# INIR2-ME5Mount.net
KiCad netlist of a schematic drawn in EAGLE
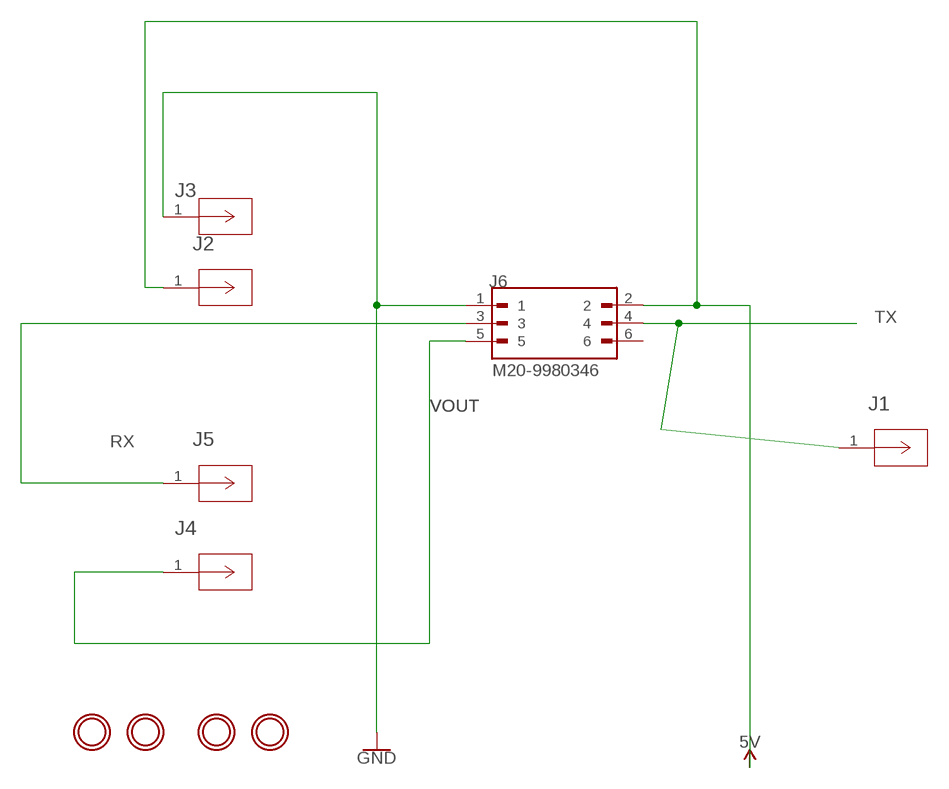
[diagram p0: schematic, sheet 1]

(export (version "E")
  (design (tool "Eeschema 10.0.6"))
  (components
    (comp (ref "J1")
      (value "450-3326-01-03-00")
      (footprint "eagle-import:CONN_450-3326-01-XX-00_CBN")
      (fields (field (name "COPYRIGHT") "Copyright (C) 2024 Ultra Librarian. All rights reserved."))
      (libsource (lib "eagle-import") (part "450-3326-01-03-00"))
    )
    (comp (ref "J2")
      (value "450-3326-01-03-00")
      (footprint "eagle-import:CONN_450-3326-01-XX-00_CBN")
      (fields (field (name "COPYRIGHT") "Copyright (C) 2024 Ultra Librarian. All rights reserved."))
      (libsource (lib "eagle-import") (part "450-3326-01-03-00"))
    )
    (comp (ref "J3")
      (value "450-3326-01-03-00")
      (footprint "eagle-import:CONN_450-3326-01-XX-00_CBN")
      (fields (field (name "COPYRIGHT") "Copyright (C) 2024 Ultra Librarian. All rights reserved."))
      (libsource (lib "eagle-import") (part "450-3326-01-03-00"))
    )
    (comp (ref "J4")
      (value "450-3326-01-03-00")
      (footprint "eagle-import:CONN_450-3326-01-XX-00_CBN")
      (fields (field (name "COPYRIGHT") "Copyright (C) 2024 Ultra Librarian. All rights reserved."))
      (libsource (lib "eagle-import") (part "450-3326-01-03-00"))
    )
    (comp (ref "J5")
      (value "450-3326-01-03-00")
      (footprint "eagle-import:CONN_450-3326-01-XX-00_CBN")
      (fields (field (name "COPYRIGHT") "Copyright (C) 2024 Ultra Librarian. All rights reserved."))
      (libsource (lib "eagle-import") (part "450-3326-01-03-00"))
    )
    (comp (ref "J6")
      (value "M20-9980346")
      (footprint "eagle-import:HARWIN_M20-9980346")
      (fields (field (name "MANUFACTURER") "HARWIN"))
      (libsource (lib "eagle-import") (part "M20-9980346"))
    )
    (comp (ref "U$1")
      (value "MOUNTINGHOLE2.5")
      (footprint "eagle-import:MOUNTINGHOLE_2.5_PLATED")
      (libsource (lib "eagle-import") (part "MOUNTINGHOLE2.5"))
    )
    (comp (ref "U$2")
      (value "MOUNTINGHOLE2.5")
      (footprint "eagle-import:MOUNTINGHOLE_2.5_PLATED")
      (libsource (lib "eagle-import") (part "MOUNTINGHOLE2.5"))
    )
    (comp (ref "U$3")
      (value "MOUNTINGHOLE2.5")
      (footprint "eagle-import:MOUNTINGHOLE_2.5_PLATED")
      (libsource (lib "eagle-import") (part "MOUNTINGHOLE2.5"))
    )
    (comp (ref "U$4")
      (value "MOUNTINGHOLE2.5")
      (footprint "eagle-import:MOUNTINGHOLE_2.5_PLATED")
      (libsource (lib "eagle-import") (part "MOUNTINGHOLE2.5"))
    )
  )
  (nets
    (net (code "1") (name "/RX") (class "Default")
      (node (ref "J5") (pin "1") (pinfunction "1_1") (pintype "passive"))
      (node (ref "J6") (pin "3") (pinfunction "3_3") (pintype "passive"))
    )
    (net (code "2") (name "/TX") (class "Default")
      (node (ref "J1") (pin "1") (pinfunction "1_1") (pintype "passive"))
      (node (ref "J6") (pin "4") (pinfunction "4_4") (pintype "passive"))
    )
    (net (code "3") (name "/VOUT") (class "Default")
      (node (ref "J4") (pin "1") (pinfunction "1_1") (pintype "passive"))
      (node (ref "J6") (pin "5") (pinfunction "5_5") (pintype "passive"))
    )
    (net (code "4") (name "5V") (class "Default")
      (node (ref "J2") (pin "1") (pinfunction "1_1") (pintype "passive"))
      (node (ref "J6") (pin "2") (pinfunction "2_2") (pintype "passive"))
    )
    (net (code "5") (name "GND") (class "Default")
      (node (ref "J3") (pin "1") (pinfunction "1_1") (pintype "passive"))
      (node (ref "J6") (pin "1") (pinfunction "1_1") (pintype "passive"))
    )
    (net (code "6") (name "unconnected-(J6-Pad6)") (class "Default")
      (node (ref "J6") (pin "6") (pinfunction "6_6") (pintype "passive"))
    )
  )
)
